# Whistler_Schematic_RevE.net
KiCad netlist of a schematic drawn in EAGLE
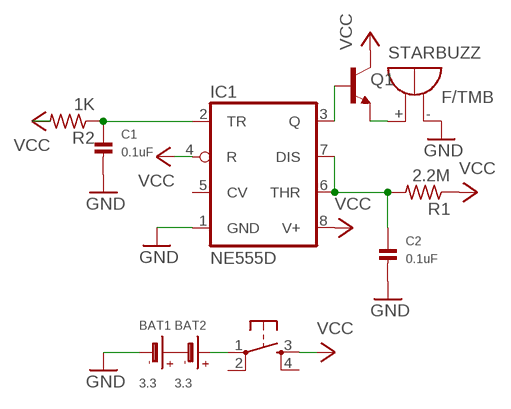
[diagram p0: schematic, sheet 1]

(export (version "E")
  (design (tool "Eeschema 10.0.6"))
  (components
    (comp (ref "BAT1")
      (value "3.3")
      (footprint "eagle-import:CR1220")
      (libsource (lib "eagle-import") (part "BATTERYCR1220_SMT"))
    )
    (comp (ref "BAT2")
      (value "3.3")
      (footprint "eagle-import:CR1220")
      (libsource (lib "eagle-import") (part "BATTERYCR1220_SMT"))
    )
    (comp (ref "C1")
      (value "0.1uF")
      (footprint "eagle-import:_0805")
      (libsource (lib "eagle-import") (part "CAP_CERAMIC_0805"))
    )
    (comp (ref "C2")
      (value "0.1uF")
      (footprint "eagle-import:_0805")
      (libsource (lib "eagle-import") (part "CAP_CERAMIC_0805"))
    )
    (comp (ref "IC1")
      (value "NE555D")
      (footprint "eagle-import:SO08")
      (libsource (lib "eagle-import") (part "555DNE"))
    )
    (comp (ref "Q1")
      (value "TRANS_NPN-MMBT2222AL")
      (footprint "eagle-import:SOT23-3")
      (libsource (lib "eagle-import") (part "TRANS_NPN-MMBT2222AL"))
    )
    (comp (ref "R1")
      (value "2.2M")
      (footprint "eagle-import:R1206")
      (libsource (lib "eagle-import") (part "R-US_R1206"))
    )
    (comp (ref "R2")
      (value "1K")
      (footprint "eagle-import:R1206")
      (libsource (lib "eagle-import") (part "R-US_R1206"))
    )
    (comp (ref "S2")
      (value "TAC_SWITCHSMD")
      (footprint "eagle-import:TACTILE-SWITCH-SMD")
      (libsource (lib "eagle-import") (part "TAC_SWITCHSMD"))
    )
    (comp (ref "STARBUZZ")
      (value "F/TMB")
      (footprint "eagle-import:F_TMB")
      (libsource (lib "eagle-import") (part "F/TMB"))
    )
  )
  (nets
    (net (code "1") (name "GND") (class "Default")
      (node (ref "BAT1") (pin "-") (pinfunction "-_-") (pintype "passive"))
      (node (ref "C1") (pin "2") (pinfunction "P$2_2") (pintype "passive"))
      (node (ref "C2") (pin "2") (pinfunction "P$2_2") (pintype "passive"))
      (node (ref "IC1") (pin "1") (pinfunction "GND_1") (pintype "power_in"))
      (node (ref "STARBUZZ") (pin "-") (pinfunction "-_-") (pintype "passive"))
    )
    (net (code "2") (name "Net-(BAT1-+)") (class "Default")
      (node (ref "BAT1") (pin "+$1") (pinfunction "+_+$1") (pintype "passive"))
      (node (ref "BAT2") (pin "-") (pinfunction "-_-") (pintype "passive"))
    )
    (net (code "3") (name "Net-(BAT2-+)") (class "Default")
      (node (ref "BAT2") (pin "+$1") (pinfunction "+_+$1") (pintype "passive"))
      (node (ref "S2") (pin "1") (pinfunction "1_1") (pintype "passive"))
    )
    (net (code "4") (name "Net-(C1-P$1)") (class "Default")
      (node (ref "C1") (pin "1") (pinfunction "P$1_1") (pintype "passive"))
      (node (ref "IC1") (pin "2") (pinfunction "TR_2") (pintype "input"))
      (node (ref "R2") (pin "1") (pinfunction "1_1") (pintype "passive"))
    )
    (net (code "5") (name "Net-(C2-P$1)") (class "Default")
      (node (ref "C2") (pin "1") (pinfunction "P$1_1") (pintype "passive"))
      (node (ref "IC1") (pin "6") (pinfunction "THR_6") (pintype "input"))
      (node (ref "IC1") (pin "7") (pinfunction "DIS_7") (pintype "input"))
      (node (ref "R1") (pin "2") (pinfunction "2_2") (pintype "passive"))
    )
    (net (code "6") (name "Net-(IC1-Q)") (class "Default")
      (node (ref "IC1") (pin "3") (pinfunction "Q_3") (pintype "output"))
      (node (ref "Q1") (pin "1") (pinfunction "B_1") (pintype "passive"))
    )
    (net (code "7") (name "Net-(Q1-E)") (class "Default")
      (node (ref "Q1") (pin "2") (pinfunction "E_2") (pintype "passive"))
      (node (ref "STARBUZZ") (pin "+") (pinfunction "+_+") (pintype "passive"))
    )
    (net (code "8") (name "VCC") (class "Default")
      (node (ref "IC1") (pin "4") (pinfunction "R_4") (pintype "input"))
      (node (ref "IC1") (pin "8") (pinfunction "V+_8") (pintype "power_in"))
      (node (ref "Q1") (pin "3") (pinfunction "C_3") (pintype "passive"))
      (node (ref "R1") (pin "1") (pinfunction "1_1") (pintype "passive"))
      (node (ref "R2") (pin "2") (pinfunction "2_2") (pintype "passive"))
      (node (ref "S2") (pin "3") (pinfunction "3_3") (pintype "passive"))
    )
    (net (code "9") (name "unconnected-(IC1-CV-Pad5)") (class "Default")
      (node (ref "IC1") (pin "5") (pinfunction "CV_5") (pintype "input"))
    )
    (net (code "10") (name "unconnected-(S2-Pad2)") (class "Default")
      (node (ref "S2") (pin "2") (pinfunction "2_2") (pintype "passive"))
    )
    (net (code "11") (name "unconnected-(S2-Pad4)") (class "Default")
      (node (ref "S2") (pin "4") (pinfunction "4_4") (pintype "passive"))
    )
  )
)
